# IOBoard.net
KiCad netlist of a schematic drawn in EAGLE
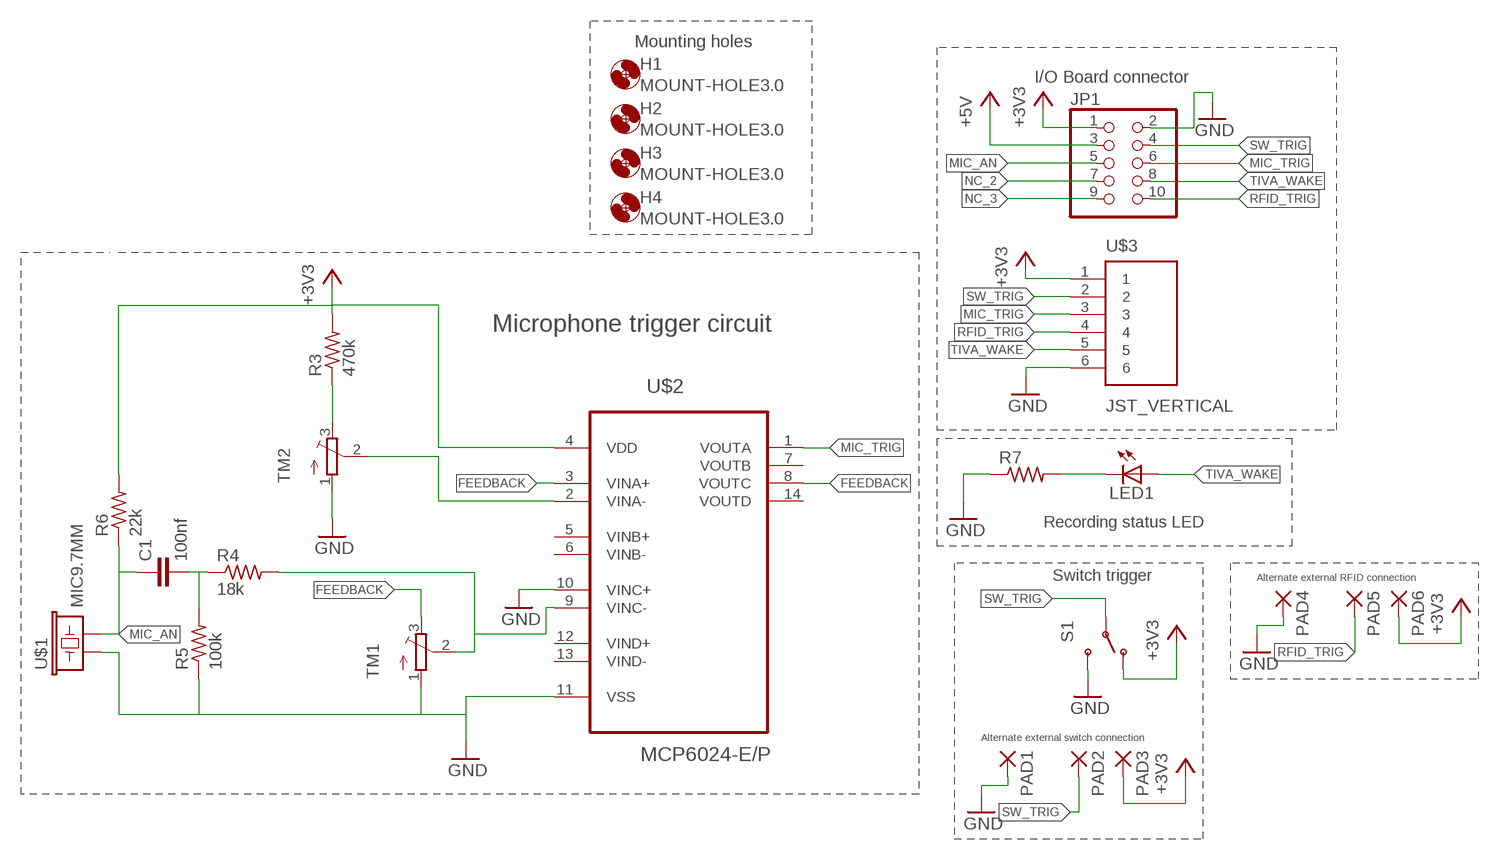
[diagram p0: schematic, sheet 1]

(export (version "E")
  (design (tool "Eeschema 10.0.6"))
  (components
    (comp (ref "C1")
      (value "100nf")
      (footprint "eagle-import:C0603")
      (libsource (lib "eagle-import") (part "C-EUC0603"))
    )
    (comp (ref "H1")
      (value "MOUNT-HOLE3.0")
      (footprint "eagle-import:3,0")
      (libsource (lib "eagle-import") (part "MOUNT-HOLE3.0"))
    )
    (comp (ref "H2")
      (value "MOUNT-HOLE3.0")
      (footprint "eagle-import:3,0")
      (libsource (lib "eagle-import") (part "MOUNT-HOLE3.0"))
    )
    (comp (ref "H3")
      (value "MOUNT-HOLE3.0")
      (footprint "eagle-import:3,0")
      (libsource (lib "eagle-import") (part "MOUNT-HOLE3.0"))
    )
    (comp (ref "H4")
      (value "MOUNT-HOLE3.0")
      (footprint "eagle-import:3,0")
      (libsource (lib "eagle-import") (part "MOUNT-HOLE3.0"))
    )
    (comp (ref "JP1")
      (value "PINHD-2X5")
      (footprint "eagle-import:2X05")
      (libsource (lib "eagle-import") (part "PINHD-2X5"))
    )
    (comp (ref "LED1")
      (value "LED10MM")
      (footprint "eagle-import:LED10MM")
      (libsource (lib "eagle-import") (part "LED10MM"))
    )
    (comp (ref "PAD1")
      (value "2,54/1,0")
      (footprint "eagle-import:2,54_1,0")
      (libsource (lib "eagle-import") (part "2,54/1,0"))
    )
    (comp (ref "PAD2")
      (value "2,54/1,0")
      (footprint "eagle-import:2,54_1,0")
      (libsource (lib "eagle-import") (part "2,54/1,0"))
    )
    (comp (ref "PAD3")
      (value "2,54/1,0")
      (footprint "eagle-import:2,54_1,0")
      (libsource (lib "eagle-import") (part "2,54/1,0"))
    )
    (comp (ref "PAD4")
      (value "2,54/1,0")
      (footprint "eagle-import:2,54_1,0")
      (libsource (lib "eagle-import") (part "2,54/1,0"))
    )
    (comp (ref "PAD5")
      (value "2,54/1,0")
      (footprint "eagle-import:2,54_1,0")
      (libsource (lib "eagle-import") (part "2,54/1,0"))
    )
    (comp (ref "PAD6")
      (value "2,54/1,0")
      (footprint "eagle-import:2,54_1,0")
      (libsource (lib "eagle-import") (part "2,54/1,0"))
    )
    (comp (ref "R3")
      (value "470k")
      (footprint "eagle-import:R0603")
      (libsource (lib "eagle-import") (part "R-US_R0603"))
    )
    (comp (ref "R4")
      (value "18k")
      (footprint "eagle-import:R0603")
      (libsource (lib "eagle-import") (part "R-US_R0603"))
    )
    (comp (ref "R5")
      (value "100k")
      (footprint "eagle-import:R0603")
      (libsource (lib "eagle-import") (part "R-US_R0603"))
    )
    (comp (ref "R6")
      (value "22k")
      (footprint "eagle-import:R0603")
      (libsource (lib "eagle-import") (part "R-US_R0603"))
    )
    (comp (ref "R7")
      (value "R-US_R0603")
      (footprint "eagle-import:R0603")
      (libsource (lib "eagle-import") (part "R-US_R0603"))
    )
    (comp (ref "S1")
      (value "SWITCH-SPDTPTH")
      (footprint "eagle-import:SWITCH-SPDT")
      (libsource (lib "eagle-import") (part "SWITCH-SPDTPTH"))
    )
    (comp (ref "TM1")
      (value "TRIMPOTTC33X")
      (footprint "eagle-import:TC33X")
      (libsource (lib "eagle-import") (part "TRIMPOTTC33X"))
    )
    (comp (ref "TM2")
      (value "TRIMPOTTC33X")
      (footprint "eagle-import:TC33X")
      (libsource (lib "eagle-import") (part "TRIMPOTTC33X"))
    )
    (comp (ref "U$1")
      (value "MIC9.7MM")
      (footprint "eagle-import:MIC-9.7MM")
      (libsource (lib "eagle-import") (part "MIC9.7MM"))
    )
    (comp (ref "U$2")
      (value "MCP6024-E/P")
      (footprint "eagle-import:DIP254P762X533-14")
      (libsource (lib "eagle-import") (part "MCP6024-E/P"))
    )
    (comp (ref "U$3")
      (value "JST_VERTICAL")
      (footprint "eagle-import:JST-6-SMD-VERT-1.0MM")
      (libsource (lib "eagle-import") (part "JST_VERTICAL"))
    )
  )
  (nets
    (net (code "1") (name "+3V3") (class "Default")
      (node (ref "JP1") (pin "1") (pinfunction "1_1") (pintype "passive"))
      (node (ref "PAD3") (pin "1") (pinfunction "P_1") (pintype "passive"))
      (node (ref "PAD6") (pin "1") (pinfunction "P_1") (pintype "passive"))
      (node (ref "R3") (pin "2") (pinfunction "2_2") (pintype "passive"))
      (node (ref "R6") (pin "2") (pinfunction "2_2") (pintype "passive"))
      (node (ref "S1") (pin "1") (pinfunction "O_1") (pintype "passive"))
      (node (ref "U$2") (pin "4") (pinfunction "VDD_4") (pintype "power_in"))
      (node (ref "U$3") (pin "1") (pinfunction "1_1") (pintype "bidirectional"))
    )
    (net (code "2") (name "+5V") (class "Default")
      (node (ref "JP1") (pin "3") (pinfunction "3_3") (pintype "passive"))
    )
    (net (code "3") (name "FEEDBACK") (class "Default")
      (node (ref "TM1") (pin "3") (pinfunction "E_3") (pintype "passive"))
      (node (ref "U$2") (pin "3") (pinfunction "VINA+_3") (pintype "input"))
      (node (ref "U$2") (pin "8") (pinfunction "VOUTC_8") (pintype "output"))
    )
    (net (code "4") (name "GND") (class "Default")
      (node (ref "JP1") (pin "2") (pinfunction "2_2") (pintype "passive"))
      (node (ref "PAD1") (pin "1") (pinfunction "P_1") (pintype "passive"))
      (node (ref "PAD4") (pin "1") (pinfunction "P_1") (pintype "passive"))
      (node (ref "R5") (pin "1") (pinfunction "1_1") (pintype "passive"))
      (node (ref "R7") (pin "1") (pinfunction "1_1") (pintype "passive"))
      (node (ref "S1") (pin "3") (pinfunction "S_3") (pintype "passive"))
      (node (ref "TM1") (pin "1") (pinfunction "A_1") (pintype "passive"))
      (node (ref "TM2") (pin "1") (pinfunction "A_1") (pintype "passive"))
      (node (ref "U$1") (pin "1") (pinfunction "1_1") (pintype "passive"))
      (node (ref "U$2") (pin "10") (pinfunction "VINC+_10") (pintype "input"))
      (node (ref "U$2") (pin "11") (pinfunction "VSS_11") (pintype "power_in"))
      (node (ref "U$3") (pin "6") (pinfunction "6_6") (pintype "bidirectional"))
    )
    (net (code "5") (name "MIC_AN") (class "Default")
      (node (ref "C1") (pin "1") (pinfunction "1_1") (pintype "passive"))
      (node (ref "JP1") (pin "5") (pinfunction "5_5") (pintype "passive"))
      (node (ref "R6") (pin "1") (pinfunction "1_1") (pintype "passive"))
      (node (ref "U$1") (pin "2") (pinfunction "2_2") (pintype "passive"))
    )
    (net (code "6") (name "MIC_TRIG") (class "Default")
      (node (ref "JP1") (pin "6") (pinfunction "6_6") (pintype "passive"))
      (node (ref "U$2") (pin "1") (pinfunction "VOUTA_1") (pintype "output"))
      (node (ref "U$3") (pin "3") (pinfunction "3_3") (pintype "bidirectional"))
    )
    (net (code "7") (name "NC_2") (class "Default")
      (node (ref "JP1") (pin "7") (pinfunction "7_7") (pintype "passive"))
    )
    (net (code "8") (name "NC_3") (class "Default")
      (node (ref "JP1") (pin "9") (pinfunction "9_9") (pintype "passive"))
    )
    (net (code "9") (name "Net-(C1-Pad2)") (class "Default")
      (node (ref "C1") (pin "2") (pinfunction "2_2") (pintype "passive"))
      (node (ref "R4") (pin "1") (pinfunction "1_1") (pintype "passive"))
      (node (ref "R5") (pin "2") (pinfunction "2_2") (pintype "passive"))
    )
    (net (code "10") (name "Net-(LED1-C)") (class "Default")
      (node (ref "LED1") (pin "K") (pinfunction "C_K") (pintype "passive"))
      (node (ref "R7") (pin "2") (pinfunction "2_2") (pintype "passive"))
    )
    (net (code "11") (name "Net-(TM1-S)") (class "Default")
      (node (ref "R4") (pin "2") (pinfunction "2_2") (pintype "passive"))
      (node (ref "TM1") (pin "2") (pinfunction "S_2") (pintype "passive"))
      (node (ref "U$2") (pin "9") (pinfunction "VINC-_9") (pintype "input"))
    )
    (net (code "12") (name "Net-(TM2-E)") (class "Default")
      (node (ref "R3") (pin "1") (pinfunction "1_1") (pintype "passive"))
      (node (ref "TM2") (pin "3") (pinfunction "E_3") (pintype "passive"))
    )
    (net (code "13") (name "Net-(TM2-S)") (class "Default")
      (node (ref "TM2") (pin "2") (pinfunction "S_2") (pintype "passive"))
      (node (ref "U$2") (pin "2") (pinfunction "VINA-_2") (pintype "input"))
    )
    (net (code "14") (name "RFID_TRIG") (class "Default")
      (node (ref "JP1") (pin "10") (pinfunction "10_10") (pintype "passive"))
      (node (ref "PAD5") (pin "1") (pinfunction "P_1") (pintype "passive"))
      (node (ref "U$3") (pin "4") (pinfunction "4_4") (pintype "bidirectional"))
    )
    (net (code "15") (name "SW_TRIG") (class "Default")
      (node (ref "JP1") (pin "4") (pinfunction "4_4") (pintype "passive"))
      (node (ref "PAD2") (pin "1") (pinfunction "P_1") (pintype "passive"))
      (node (ref "S1") (pin "2") (pinfunction "P_2") (pintype "passive"))
      (node (ref "U$3") (pin "2") (pinfunction "2_2") (pintype "bidirectional"))
    )
    (net (code "16") (name "TIVA_WAKE") (class "Default")
      (node (ref "JP1") (pin "8") (pinfunction "8_8") (pintype "passive"))
      (node (ref "LED1") (pin "A") (pinfunction "A_A") (pintype "passive"))
      (node (ref "U$3") (pin "5") (pinfunction "5_5") (pintype "bidirectional"))
    )
    (net (code "17") (name "unconnected-(U$2-VINB+-Pad5)") (class "Default")
      (node (ref "U$2") (pin "5") (pinfunction "VINB+_5") (pintype "input"))
    )
    (net (code "18") (name "unconnected-(U$2-VINB--Pad6)") (class "Default")
      (node (ref "U$2") (pin "6") (pinfunction "VINB-_6") (pintype "input"))
    )
    (net (code "19") (name "unconnected-(U$2-VIND+-Pad12)") (class "Default")
      (node (ref "U$2") (pin "12") (pinfunction "VIND+_12") (pintype "input"))
    )
    (net (code "20") (name "unconnected-(U$2-VIND--Pad13)") (class "Default")
      (node (ref "U$2") (pin "13") (pinfunction "VIND-_13") (pintype "input"))
    )
    (net (code "21") (name "unconnected-(U$2-VOUTB-Pad7)") (class "Default")
      (node (ref "U$2") (pin "7") (pinfunction "VOUTB_7") (pintype "output"))
    )
    (net (code "22") (name "unconnected-(U$2-VOUTD-Pad14)") (class "Default")
      (node (ref "U$2") (pin "14") (pinfunction "VOUTD_14") (pintype "output"))
    )
  )
)
